# DaysSince.net
KiCad netlist of a schematic drawn in EAGLE
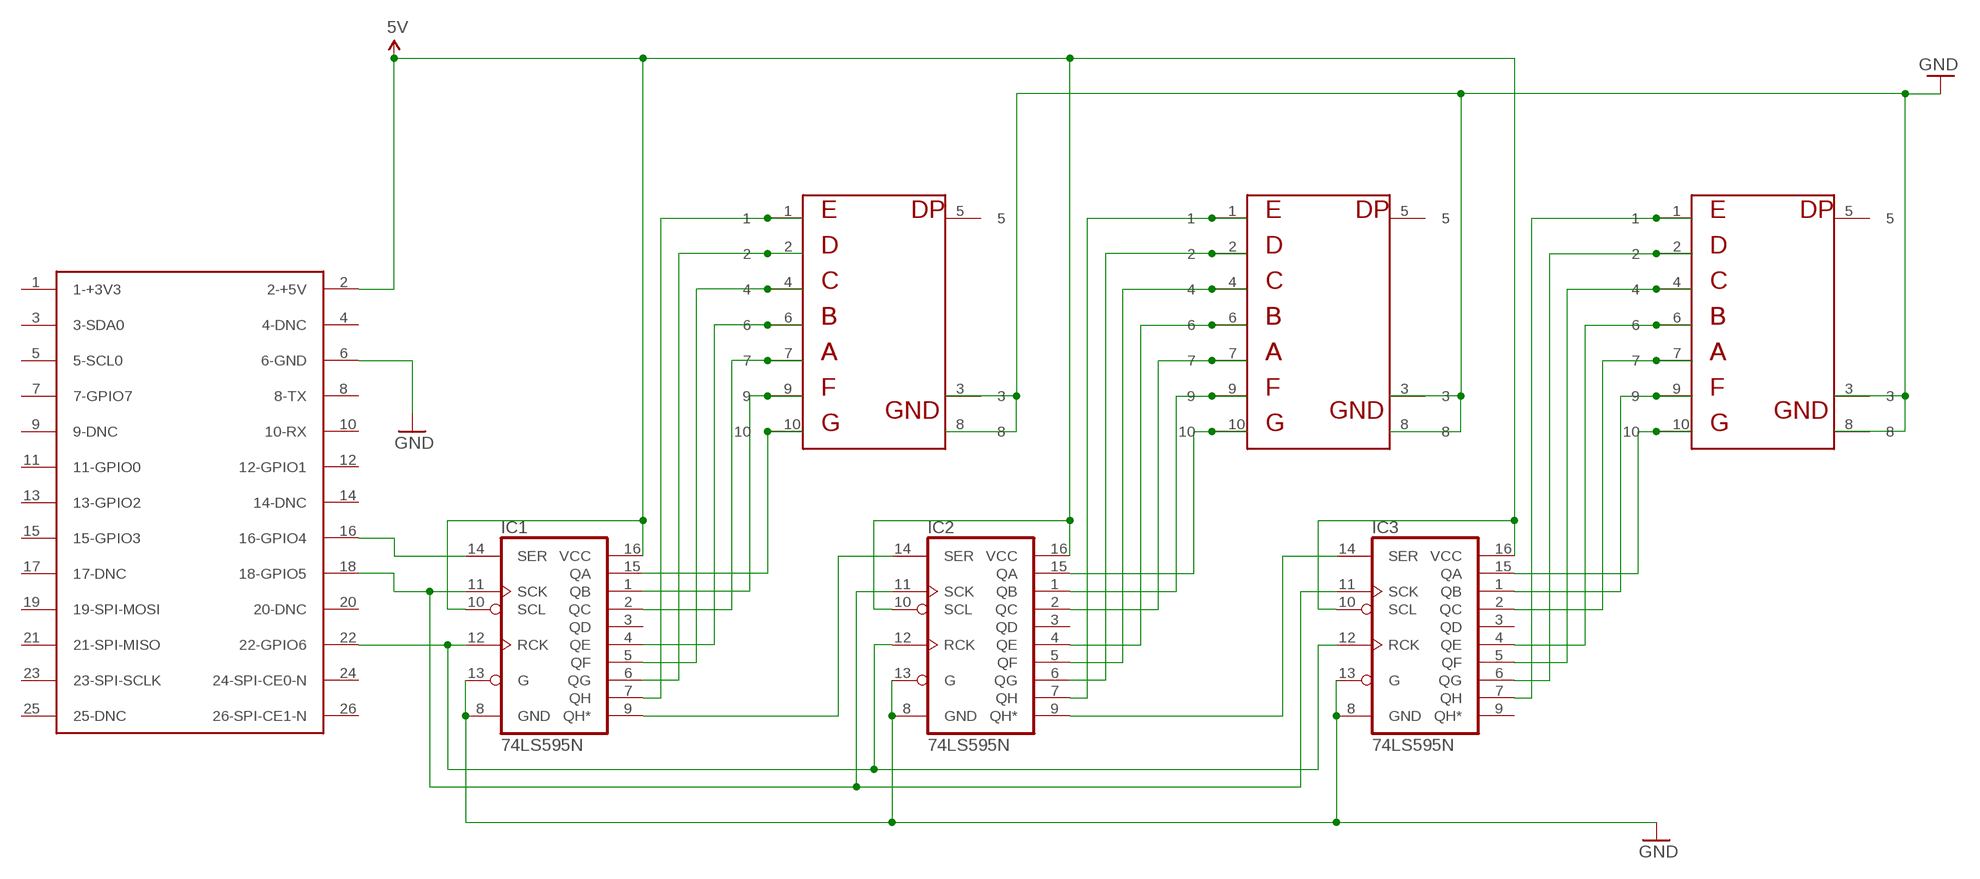
[diagram p0: schematic, sheet 1]

(export (version "E")
  (design (tool "Eeschema 10.0.6"))
  (components
    (comp (ref "IC1")
      (value "74LS595N")
      (footprint "eagle-import:DIL16")
      (libsource (lib "eagle-import") (part "74595NLS"))
    )
    (comp (ref "IC2")
      (value "74LS595N")
      (footprint "eagle-import:DIL16")
      (libsource (lib "eagle-import") (part "74595NLS"))
    )
    (comp (ref "IC3")
      (value "74LS595N")
      (footprint "eagle-import:DIL16")
      (libsource (lib "eagle-import") (part "74595NLS"))
    )
    (comp (ref "LED1")
      (value "7SG100012AG")
      (footprint "eagle-import:7SG100012AG")
      (libsource (lib "eagle-import") (part "7SG100012AG"))
    )
    (comp (ref "LED2")
      (value "7SG100012AG")
      (footprint "eagle-import:7SG100012AG")
      (libsource (lib "eagle-import") (part "7SG100012AG"))
    )
    (comp (ref "LED3")
      (value "7SG100012AG")
      (footprint "eagle-import:7SG100012AG")
      (libsource (lib "eagle-import") (part "7SG100012AG"))
    )
    (comp (ref "U$1")
      (value "RASPBERRY-PI")
      (footprint "eagle-import:RASPBERRY-PI")
      (libsource (lib "eagle-import") (part "RASPBERRY-PI"))
    )
  )
  (nets
    (net (code "1") (name "5V") (class "Default")
      (node (ref "IC1") (pin "10") (pinfunction "SCL_10") (pintype "input"))
      (node (ref "IC1") (pin "16") (pinfunction "VCC_16") (pintype "power_in"))
      (node (ref "IC2") (pin "10") (pinfunction "SCL_10") (pintype "input"))
      (node (ref "IC2") (pin "16") (pinfunction "VCC_16") (pintype "power_in"))
      (node (ref "IC3") (pin "10") (pinfunction "SCL_10") (pintype "input"))
      (node (ref "IC3") (pin "16") (pinfunction "VCC_16") (pintype "power_in"))
      (node (ref "U$1") (pin "2") (pinfunction "2-+5V_2") (pintype "bidirectional"))
    )
    (net (code "2") (name "GND") (class "Default")
      (node (ref "IC1") (pin "13") (pinfunction "G_13") (pintype "input"))
      (node (ref "IC1") (pin "8") (pinfunction "GND_8") (pintype "power_in"))
      (node (ref "IC2") (pin "13") (pinfunction "G_13") (pintype "input"))
      (node (ref "IC2") (pin "8") (pinfunction "GND_8") (pintype "power_in"))
      (node (ref "IC3") (pin "13") (pinfunction "G_13") (pintype "input"))
      (node (ref "IC3") (pin "8") (pinfunction "GND_8") (pintype "power_in"))
      (node (ref "LED1") (pin "3") (pinfunction "3_3") (pintype "bidirectional"))
      (node (ref "LED1") (pin "8") (pinfunction "8_8") (pintype "bidirectional"))
      (node (ref "LED2") (pin "3") (pinfunction "3_3") (pintype "bidirectional"))
      (node (ref "LED2") (pin "8") (pinfunction "8_8") (pintype "bidirectional"))
      (node (ref "LED3") (pin "3") (pinfunction "3_3") (pintype "bidirectional"))
      (node (ref "LED3") (pin "8") (pinfunction "8_8") (pintype "bidirectional"))
      (node (ref "U$1") (pin "6") (pinfunction "6-GND_6") (pintype "bidirectional"))
    )
    (net (code "3") (name "Net-(IC1-QA)") (class "Default")
      (node (ref "IC1") (pin "15") (pinfunction "QA_15") (pintype "tri_state"))
      (node (ref "LED1") (pin "10") (pinfunction "10_10") (pintype "bidirectional"))
    )
    (net (code "4") (name "Net-(IC1-QB)") (class "Default")
      (node (ref "IC1") (pin "1") (pinfunction "QB_1") (pintype "tri_state"))
      (node (ref "LED1") (pin "9") (pinfunction "9_9") (pintype "bidirectional"))
    )
    (net (code "5") (name "Net-(IC1-QC)") (class "Default")
      (node (ref "IC1") (pin "2") (pinfunction "QC_2") (pintype "tri_state"))
      (node (ref "LED1") (pin "7") (pinfunction "7_7") (pintype "bidirectional"))
    )
    (net (code "6") (name "Net-(IC1-QE)") (class "Default")
      (node (ref "IC1") (pin "4") (pinfunction "QE_4") (pintype "tri_state"))
      (node (ref "LED1") (pin "6") (pinfunction "6_6") (pintype "bidirectional"))
    )
    (net (code "7") (name "Net-(IC1-QF)") (class "Default")
      (node (ref "IC1") (pin "5") (pinfunction "QF_5") (pintype "tri_state"))
      (node (ref "LED1") (pin "4") (pinfunction "4_4") (pintype "bidirectional"))
    )
    (net (code "8") (name "Net-(IC1-QG)") (class "Default")
      (node (ref "IC1") (pin "6") (pinfunction "QG_6") (pintype "tri_state"))
      (node (ref "LED1") (pin "2") (pinfunction "2_2") (pintype "bidirectional"))
    )
    (net (code "9") (name "Net-(IC1-QH)") (class "Default")
      (node (ref "IC1") (pin "7") (pinfunction "QH_7") (pintype "tri_state"))
      (node (ref "LED1") (pin "1") (pinfunction "1_1") (pintype "bidirectional"))
    )
    (net (code "10") (name "Net-(IC1-QH*)") (class "Default")
      (node (ref "IC1") (pin "9") (pinfunction "QH*_9") (pintype "tri_state"))
      (node (ref "IC2") (pin "14") (pinfunction "SER_14") (pintype "input"))
    )
    (net (code "11") (name "Net-(IC1-RCK)") (class "Default")
      (node (ref "IC1") (pin "12") (pinfunction "RCK_12") (pintype "input"))
      (node (ref "IC2") (pin "12") (pinfunction "RCK_12") (pintype "input"))
      (node (ref "IC3") (pin "12") (pinfunction "RCK_12") (pintype "input"))
      (node (ref "U$1") (pin "22") (pinfunction "22-GPIO6_22") (pintype "bidirectional"))
    )
    (net (code "12") (name "Net-(IC1-SCK)") (class "Default")
      (node (ref "IC1") (pin "11") (pinfunction "SCK_11") (pintype "input"))
      (node (ref "IC2") (pin "11") (pinfunction "SCK_11") (pintype "input"))
      (node (ref "IC3") (pin "11") (pinfunction "SCK_11") (pintype "input"))
      (node (ref "U$1") (pin "18") (pinfunction "18-GPIO5_18") (pintype "bidirectional"))
    )
    (net (code "13") (name "Net-(IC1-SER)") (class "Default")
      (node (ref "IC1") (pin "14") (pinfunction "SER_14") (pintype "input"))
      (node (ref "U$1") (pin "16") (pinfunction "16-GPIO4_16") (pintype "bidirectional"))
    )
    (net (code "14") (name "Net-(IC2-QA)") (class "Default")
      (node (ref "IC2") (pin "15") (pinfunction "QA_15") (pintype "tri_state"))
      (node (ref "LED2") (pin "10") (pinfunction "10_10") (pintype "bidirectional"))
    )
    (net (code "15") (name "Net-(IC2-QB)") (class "Default")
      (node (ref "IC2") (pin "1") (pinfunction "QB_1") (pintype "tri_state"))
      (node (ref "LED2") (pin "9") (pinfunction "9_9") (pintype "bidirectional"))
    )
    (net (code "16") (name "Net-(IC2-QC)") (class "Default")
      (node (ref "IC2") (pin "2") (pinfunction "QC_2") (pintype "tri_state"))
      (node (ref "LED2") (pin "7") (pinfunction "7_7") (pintype "bidirectional"))
    )
    (net (code "17") (name "Net-(IC2-QE)") (class "Default")
      (node (ref "IC2") (pin "4") (pinfunction "QE_4") (pintype "tri_state"))
      (node (ref "LED2") (pin "6") (pinfunction "6_6") (pintype "bidirectional"))
    )
    (net (code "18") (name "Net-(IC2-QF)") (class "Default")
      (node (ref "IC2") (pin "5") (pinfunction "QF_5") (pintype "tri_state"))
      (node (ref "LED2") (pin "4") (pinfunction "4_4") (pintype "bidirectional"))
    )
    (net (code "19") (name "Net-(IC2-QG)") (class "Default")
      (node (ref "IC2") (pin "6") (pinfunction "QG_6") (pintype "tri_state"))
      (node (ref "LED2") (pin "2") (pinfunction "2_2") (pintype "bidirectional"))
    )
    (net (code "20") (name "Net-(IC2-QH)") (class "Default")
      (node (ref "IC2") (pin "7") (pinfunction "QH_7") (pintype "tri_state"))
      (node (ref "LED2") (pin "1") (pinfunction "1_1") (pintype "bidirectional"))
    )
    (net (code "21") (name "Net-(IC2-QH*)") (class "Default")
      (node (ref "IC2") (pin "9") (pinfunction "QH*_9") (pintype "tri_state"))
      (node (ref "IC3") (pin "14") (pinfunction "SER_14") (pintype "input"))
    )
    (net (code "22") (name "Net-(IC3-QA)") (class "Default")
      (node (ref "IC3") (pin "15") (pinfunction "QA_15") (pintype "tri_state"))
      (node (ref "LED3") (pin "10") (pinfunction "10_10") (pintype "bidirectional"))
    )
    (net (code "23") (name "Net-(IC3-QB)") (class "Default")
      (node (ref "IC3") (pin "1") (pinfunction "QB_1") (pintype "tri_state"))
      (node (ref "LED3") (pin "9") (pinfunction "9_9") (pintype "bidirectional"))
    )
    (net (code "24") (name "Net-(IC3-QC)") (class "Default")
      (node (ref "IC3") (pin "2") (pinfunction "QC_2") (pintype "tri_state"))
      (node (ref "LED3") (pin "7") (pinfunction "7_7") (pintype "bidirectional"))
    )
    (net (code "25") (name "Net-(IC3-QE)") (class "Default")
      (node (ref "IC3") (pin "4") (pinfunction "QE_4") (pintype "tri_state"))
      (node (ref "LED3") (pin "6") (pinfunction "6_6") (pintype "bidirectional"))
    )
    (net (code "26") (name "Net-(IC3-QF)") (class "Default")
      (node (ref "IC3") (pin "5") (pinfunction "QF_5") (pintype "tri_state"))
      (node (ref "LED3") (pin "4") (pinfunction "4_4") (pintype "bidirectional"))
    )
    (net (code "27") (name "Net-(IC3-QG)") (class "Default")
      (node (ref "IC3") (pin "6") (pinfunction "QG_6") (pintype "tri_state"))
      (node (ref "LED3") (pin "2") (pinfunction "2_2") (pintype "bidirectional"))
    )
    (net (code "28") (name "Net-(IC3-QH)") (class "Default")
      (node (ref "IC3") (pin "7") (pinfunction "QH_7") (pintype "tri_state"))
      (node (ref "LED3") (pin "1") (pinfunction "1_1") (pintype "bidirectional"))
    )
    (net (code "29") (name "unconnected-(IC1-QD-Pad3)") (class "Default")
      (node (ref "IC1") (pin "3") (pinfunction "QD_3") (pintype "tri_state"))
    )
    (net (code "30") (name "unconnected-(IC2-QD-Pad3)") (class "Default")
      (node (ref "IC2") (pin "3") (pinfunction "QD_3") (pintype "tri_state"))
    )
    (net (code "31") (name "unconnected-(IC3-QD-Pad3)") (class "Default")
      (node (ref "IC3") (pin "3") (pinfunction "QD_3") (pintype "tri_state"))
    )
    (net (code "32") (name "unconnected-(IC3-QH*-Pad9)") (class "Default")
      (node (ref "IC3") (pin "9") (pinfunction "QH*_9") (pintype "tri_state"))
    )
    (net (code "33") (name "unconnected-(LED1-Pad5)") (class "Default")
      (node (ref "LED1") (pin "5") (pinfunction "5_5") (pintype "bidirectional"))
    )
    (net (code "34") (name "unconnected-(LED2-Pad5)") (class "Default")
      (node (ref "LED2") (pin "5") (pinfunction "5_5") (pintype "bidirectional"))
    )
    (net (code "35") (name "unconnected-(LED3-Pad5)") (class "Default")
      (node (ref "LED3") (pin "5") (pinfunction "5_5") (pintype "bidirectional"))
    )
    (net (code "36") (name "unconnected-(U$1-1-+3V3-Pad1)") (class "Default")
      (node (ref "U$1") (pin "1") (pinfunction "1-+3V3_1") (pintype "bidirectional"))
    )
    (net (code "37") (name "unconnected-(U$1-3-SDA0-Pad3)") (class "Default")
      (node (ref "U$1") (pin "3") (pinfunction "3-SDA0_3") (pintype "bidirectional"))
    )
    (net (code "38") (name "unconnected-(U$1-4-DNC-Pad4)") (class "Default")
      (node (ref "U$1") (pin "4") (pinfunction "4-DNC_4") (pintype "bidirectional"))
    )
    (net (code "39") (name "unconnected-(U$1-5-SCL0-Pad5)") (class "Default")
      (node (ref "U$1") (pin "5") (pinfunction "5-SCL0_5") (pintype "bidirectional"))
    )
    (net (code "40") (name "unconnected-(U$1-7-GPIO7-Pad7)") (class "Default")
      (node (ref "U$1") (pin "7") (pinfunction "7-GPIO7_7") (pintype "bidirectional"))
    )
    (net (code "41") (name "unconnected-(U$1-8-TX-Pad8)") (class "Default")
      (node (ref "U$1") (pin "8") (pinfunction "8-TX_8") (pintype "bidirectional"))
    )
    (net (code "42") (name "unconnected-(U$1-9-DNC-Pad9)") (class "Default")
      (node (ref "U$1") (pin "9") (pinfunction "9-DNC_9") (pintype "bidirectional"))
    )
    (net (code "43") (name "unconnected-(U$1-10-RX-Pad10)") (class "Default")
      (node (ref "U$1") (pin "10") (pinfunction "10-RX_10") (pintype "bidirectional"))
    )
    (net (code "44") (name "unconnected-(U$1-11-GPIO0-Pad11)") (class "Default")
      (node (ref "U$1") (pin "11") (pinfunction "11-GPIO0_11") (pintype "bidirectional"))
    )
    (net (code "45") (name "unconnected-(U$1-12-GPIO1-Pad12)") (class "Default")
      (node (ref "U$1") (pin "12") (pinfunction "12-GPIO1_12") (pintype "bidirectional"))
    )
    (net (code "46") (name "unconnected-(U$1-13-GPIO2-Pad13)") (class "Default")
      (node (ref "U$1") (pin "13") (pinfunction "13-GPIO2_13") (pintype "bidirectional"))
    )
    (net (code "47") (name "unconnected-(U$1-14-DNC-Pad14)") (class "Default")
      (node (ref "U$1") (pin "14") (pinfunction "14-DNC_14") (pintype "bidirectional"))
    )
    (net (code "48") (name "unconnected-(U$1-15-GPIO3-Pad15)") (class "Default")
      (node (ref "U$1") (pin "15") (pinfunction "15-GPIO3_15") (pintype "bidirectional"))
    )
    (net (code "49") (name "unconnected-(U$1-17-DNC-Pad17)") (class "Default")
      (node (ref "U$1") (pin "17") (pinfunction "17-DNC_17") (pintype "bidirectional"))
    )
    (net (code "50") (name "unconnected-(U$1-19-SPI-MOSI-Pad19)") (class "Default")
      (node (ref "U$1") (pin "19") (pinfunction "19-SPI-MOSI_19") (pintype "bidirectional"))
    )
    (net (code "51") (name "unconnected-(U$1-20-DNC-Pad20)") (class "Default")
      (node (ref "U$1") (pin "20") (pinfunction "20-DNC_20") (pintype "bidirectional"))
    )
    (net (code "52") (name "unconnected-(U$1-21-SPI-MISO-Pad21)") (class "Default")
      (node (ref "U$1") (pin "21") (pinfunction "21-SPI-MISO_21") (pintype "bidirectional"))
    )
    (net (code "53") (name "unconnected-(U$1-23-SPI-SCLK-Pad23)") (class "Default")
      (node (ref "U$1") (pin "23") (pinfunction "23-SPI-SCLK_23") (pintype "bidirectional"))
    )
    (net (code "54") (name "unconnected-(U$1-24-SPI-CE0-N-Pad24)") (class "Default")
      (node (ref "U$1") (pin "24") (pinfunction "24-SPI-CE0-N_24") (pintype "bidirectional"))
    )
    (net (code "55") (name "unconnected-(U$1-25-DNC-Pad25)") (class "Default")
      (node (ref "U$1") (pin "25") (pinfunction "25-DNC_25") (pintype "bidirectional"))
    )
    (net (code "56") (name "unconnected-(U$1-26-SPI-CE1-N-Pad26)") (class "Default")
      (node (ref "U$1") (pin "26") (pinfunction "26-SPI-CE1-N_26") (pintype "bidirectional"))
    )
  )
)
